# Bagryanets_2.net
KiCad netlist of a schematic drawn in Altium Designer
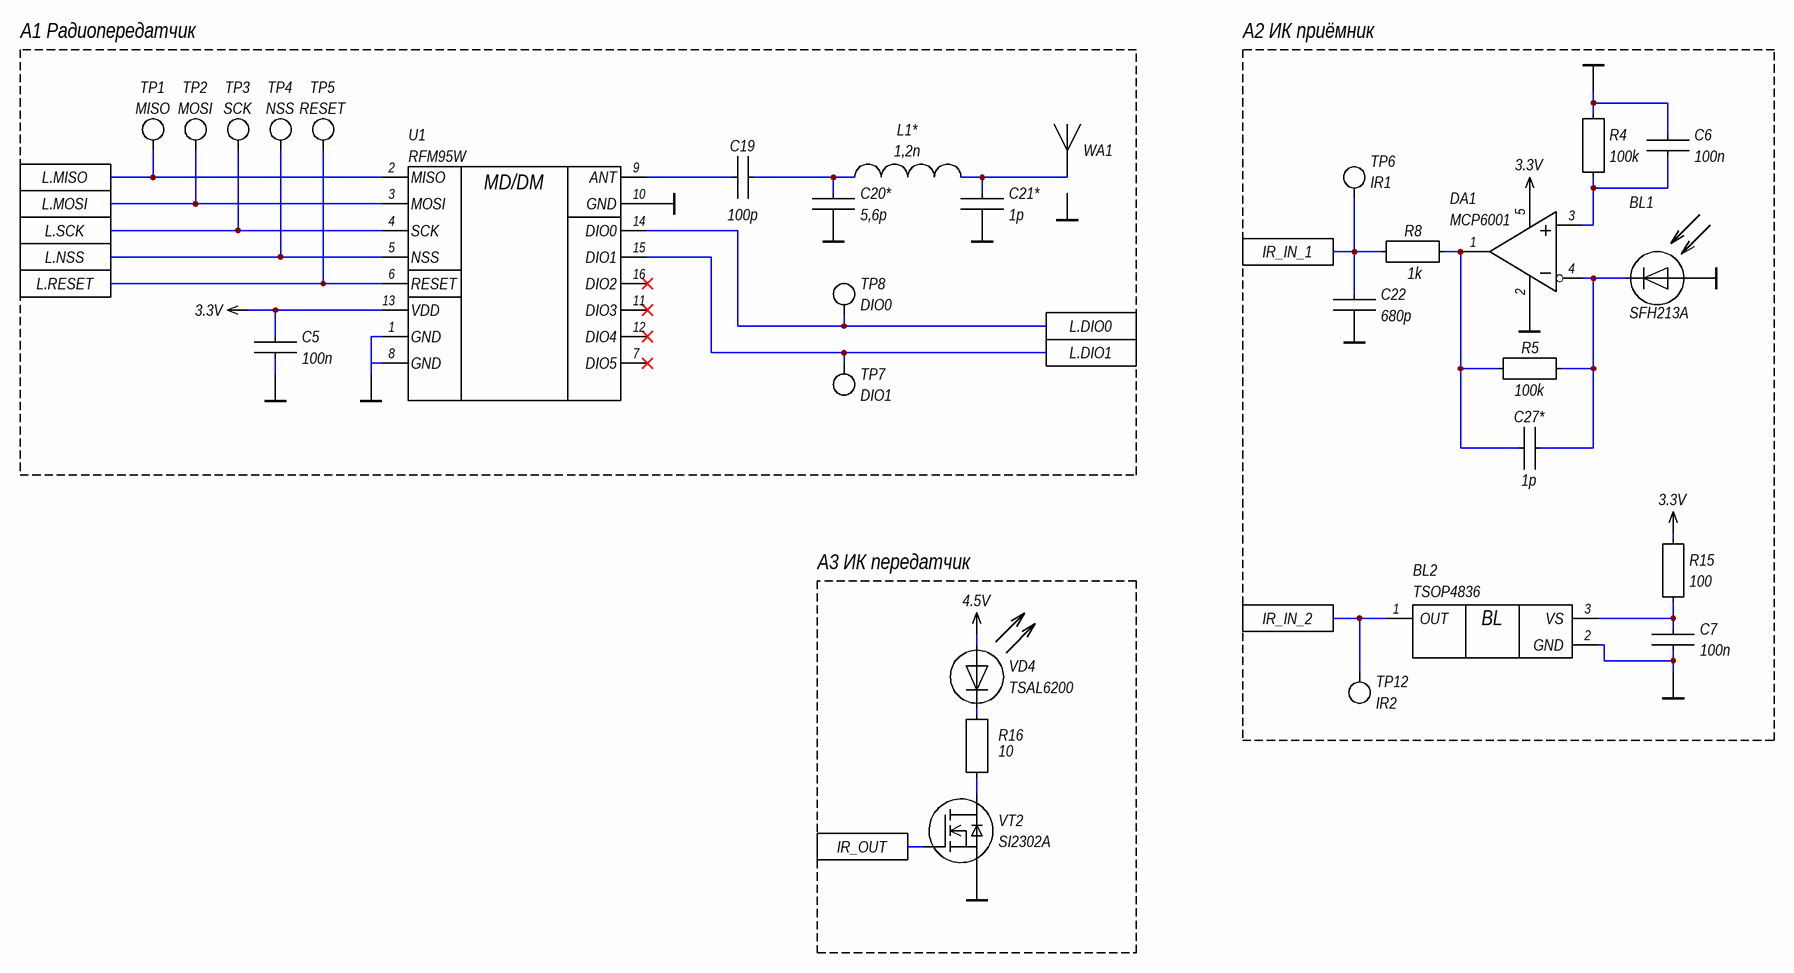
[diagram p0: Bagryanets_2.SchDoc]

(export (version "E")
  (design (tool "Eeschema 10.0.6"))
  (components
    (comp (ref "BL1")
      (value "SFH213A")
      (footprint "LED_5mm")
      (libsource (lib "Bagryanets-Schlib") (part "BL-Photodiod"))
    )
    (comp (ref "BL2")
      (value "TSOP4836")
      (footprint "TO92_TSOP4836_Horizontal")
      (libsource (lib "Bagryanets-Schlib") (part "BL-TSOP4836"))
    )
    (comp (ref "C5")
      (value "100n")
      (footprint "CAP: 0603")
      (libsource (lib "Bagryanets-Schlib") (part "C-Capacitor"))
    )
    (comp (ref "C6")
      (value "100n")
      (footprint "CAP: 0603")
      (libsource (lib "Bagryanets-Schlib") (part "C-Capacitor"))
    )
    (comp (ref "C7")
      (value "100n")
      (footprint "CAP: 0603")
      (libsource (lib "Bagryanets-Schlib") (part "C-Capacitor"))
    )
    (comp (ref "C19")
      (value "100p")
      (footprint "CAP: 0402")
      (libsource (lib "Bagryanets-Schlib") (part "C-Capacitor"))
    )
    (comp (ref "C20*")
      (value "5,6p")
      (footprint "CAP: 0402")
      (libsource (lib "Bagryanets-Schlib") (part "C-Capacitor"))
    )
    (comp (ref "C21*")
      (value "1p")
      (footprint "CAP: 0402")
      (libsource (lib "Bagryanets-Schlib") (part "C-Capacitor"))
    )
    (comp (ref "C22")
      (value "680p")
      (footprint "CAP: 0603")
      (libsource (lib "Bagryanets-Schlib") (part "C-Capacitor"))
    )
    (comp (ref "C27*")
      (value "1p")
      (footprint "CAP: 0603")
      (libsource (lib "Bagryanets-Schlib") (part "C-Capacitor"))
    )
    (comp (ref "DA1")
      (value "MCP6001")
      (footprint "SOT23-5")
      (description "IC OPAMP GP 1 CIRCUIT SOT23-5")
      (fields (field (name "VOLTAGE") "6V"))
      (libsource (lib "Bagryanets-Schlib") (part "DA-MCP6001UT-I/OT"))
    )
    (comp (ref "L1*")
      (value "1,2n")
      (footprint "IND: 0402")
      (libsource (lib "Bagryanets-Schlib") (part "L-Inductor"))
    )
    (comp (ref "R4")
      (value "100k")
      (footprint "RES: 0603")
      (libsource (lib "Bagryanets-Schlib") (part "R-Resistor"))
    )
    (comp (ref "R5")
      (value "100k")
      (footprint "RES: 0603")
      (libsource (lib "Bagryanets-Schlib") (part "R-Resistor"))
    )
    (comp (ref "R8")
      (value "1k")
      (footprint "RES: 0603")
      (libsource (lib "Bagryanets-Schlib") (part "R-Resistor"))
    )
    (comp (ref "R15")
      (value "100")
      (footprint "RES: 0603")
      (libsource (lib "Bagryanets-Schlib") (part "R-Resistor"))
    )
    (comp (ref "R16")
      (value "10")
      (footprint "RES: 0603")
      (libsource (lib "Bagryanets-Schlib") (part "R-Resistor"))
    )
    (comp (ref "TP1")
      (value "MISO")
      (footprint "Testpoint_1mm")
      (libsource (lib "Bagryanets-Schlib") (part "TP-Testpoint"))
    )
    (comp (ref "TP2")
      (value "MOSI")
      (footprint "Testpoint_1mm")
      (libsource (lib "Bagryanets-Schlib") (part "TP-Testpoint"))
    )
    (comp (ref "TP3")
      (value "SCK")
      (footprint "Testpoint_1mm")
      (libsource (lib "Bagryanets-Schlib") (part "TP-Testpoint"))
    )
    (comp (ref "TP4")
      (value "NSS")
      (footprint "Testpoint_1mm")
      (libsource (lib "Bagryanets-Schlib") (part "TP-Testpoint"))
    )
    (comp (ref "TP5")
      (value "RESET")
      (footprint "Testpoint_1mm")
      (libsource (lib "Bagryanets-Schlib") (part "TP-Testpoint"))
    )
    (comp (ref "TP6")
      (value "IR1")
      (footprint "Testpoint_1mm")
      (libsource (lib "Bagryanets-Schlib") (part "TP-Testpoint"))
    )
    (comp (ref "TP7")
      (value "DIO1")
      (footprint "Testpoint_1mm")
      (libsource (lib "Bagryanets-Schlib") (part "TP-Testpoint"))
    )
    (comp (ref "TP8")
      (value "DIO0")
      (footprint "Testpoint_1mm")
      (libsource (lib "Bagryanets-Schlib") (part "TP-Testpoint"))
    )
    (comp (ref "TP12")
      (value "IR2")
      (footprint "Testpoint_1mm")
      (libsource (lib "Bagryanets-Schlib") (part "TP-Testpoint"))
    )
    (comp (ref "U1")
      (value "RFM95W")
      (footprint "Module_RFM95W")
      (description "Rfm95W LoRa Transceiver Module 868Mhz")
      (libsource (lib "Bagryanets-Schlib") (part "MOD-RFM95W"))
    )
    (comp (ref "VD4")
      (value "TSAL6200")
      (footprint "LED_5mm")
      (libsource (lib "Bagryanets-Schlib") (part "HL-LED"))
    )
    (comp (ref "VT2")
      (value "SI2302A")
      (footprint "SOT23")
      (libsource (lib "Bagryanets-Schlib") (part "VT-N-FET-GSD"))
    )
    (comp (ref "WA1")
      (value "Antenna")
      (footprint "WA-Lora868")
      (libsource (lib "Bagryanets-Schlib") (part "WA-Antenna_2pin"))
    )
  )
  (nets
    (net (code "1") (name "/IR_IN_1") (class "Default")
      (node (ref "C22") (pin "2") (pinfunction "2_2") (pintype "passive"))
      (node (ref "R8") (pin "1") (pinfunction "1_1") (pintype "passive"))
      (node (ref "TP6") (pin "1") (pinfunction "1_1") (pintype "passive"))
    )
    (net (code "2") (name "/IR_IN_2") (class "Default")
      (node (ref "BL2") (pin "1") (pinfunction "OUT_1") (pintype "passive"))
      (node (ref "TP12") (pin "1") (pinfunction "1_1") (pintype "passive"))
    )
    (net (code "3") (name "/IR_OUT") (class "Default")
      (node (ref "VT2") (pin "1") (pinfunction "G_1") (pintype "passive"))
    )
    (net (code "4") (name "/L.DIO0") (class "Default")
      (node (ref "TP8") (pin "1") (pinfunction "1_1") (pintype "passive"))
      (node (ref "U1") (pin "14") (pinfunction "DIO0_14") (pintype "passive"))
    )
    (net (code "5") (name "/L.DIO1") (class "Default")
      (node (ref "TP7") (pin "1") (pinfunction "1_1") (pintype "passive"))
      (node (ref "U1") (pin "15") (pinfunction "DIO1_15") (pintype "passive"))
    )
    (net (code "6") (name "/L.MISO") (class "Default")
      (node (ref "TP1") (pin "1") (pinfunction "1_1") (pintype "passive"))
      (node (ref "U1") (pin "2") (pinfunction "MISO_2") (pintype "passive"))
    )
    (net (code "7") (name "/L.MOSI") (class "Default")
      (node (ref "TP2") (pin "1") (pinfunction "1_1") (pintype "passive"))
      (node (ref "U1") (pin "3") (pinfunction "MOSI_3") (pintype "passive"))
    )
    (net (code "8") (name "/L.NSS") (class "Default")
      (node (ref "TP4") (pin "1") (pinfunction "1_1") (pintype "passive"))
      (node (ref "U1") (pin "5") (pinfunction "NSS_5") (pintype "passive"))
    )
    (net (code "9") (name "/L.RESET") (class "Default")
      (node (ref "TP5") (pin "1") (pinfunction "1_1") (pintype "passive"))
      (node (ref "U1") (pin "6") (pinfunction "RESET_6") (pintype "passive"))
    )
    (net (code "10") (name "/L.SCK") (class "Default")
      (node (ref "TP3") (pin "1") (pinfunction "1_1") (pintype "passive"))
      (node (ref "U1") (pin "4") (pinfunction "SCK_4") (pintype "passive"))
    )
    (net (code "11") (name "3.3V") (class "Default")
      (node (ref "C5") (pin "2") (pinfunction "2_2") (pintype "passive"))
      (node (ref "DA1") (pin "5") (pinfunction "VDD_5") (pintype "power_in"))
      (node (ref "R15") (pin "1") (pinfunction "1_1") (pintype "passive"))
      (node (ref "U1") (pin "13") (pinfunction "VDD_13") (pintype "passive"))
    )
    (net (code "12") (name "4.5V") (class "Default")
      (node (ref "VD4") (pin "A") (pinfunction "A_A") (pintype "passive"))
    )
    (net (code "13") (name "GND") (class "Default")
      (node (ref "BL1") (pin "A") (pinfunction "A_A") (pintype "passive"))
      (node (ref "BL2") (pin "2") (pinfunction "GND_2") (pintype "power_in"))
      (node (ref "C20*") (pin "1") (pinfunction "1_1") (pintype "passive"))
      (node (ref "C21*") (pin "1") (pinfunction "1_1") (pintype "passive"))
      (node (ref "C22") (pin "1") (pinfunction "1_1") (pintype "passive"))
      (node (ref "C5") (pin "1") (pinfunction "1_1") (pintype "passive"))
      (node (ref "C6") (pin "2") (pinfunction "2_2") (pintype "passive"))
      (node (ref "C7") (pin "1") (pinfunction "1_1") (pintype "passive"))
      (node (ref "DA1") (pin "2") (pinfunction "VSS_2") (pintype "power_in"))
      (node (ref "R4") (pin "1") (pinfunction "1_1") (pintype "passive"))
      (node (ref "U1") (pin "1") (pinfunction "GND_1") (pintype "passive"))
      (node (ref "U1") (pin "10") (pinfunction "GND_10") (pintype "passive"))
      (node (ref "U1") (pin "8") (pinfunction "GND_8") (pintype "passive"))
      (node (ref "VT2") (pin "2") (pinfunction "S_2") (pintype "passive"))
      (node (ref "WA1") (pin "2") (pinfunction "2_2") (pintype "passive"))
    )
    (net (code "14") (name "Net-(BL2-VS)") (class "Default")
      (node (ref "BL2") (pin "3") (pinfunction "VS_3") (pintype "power_in"))
      (node (ref "C7") (pin "2") (pinfunction "2_2") (pintype "passive"))
      (node (ref "R15") (pin "2") (pinfunction "2_2") (pintype "passive"))
    )
    (net (code "15") (name "Net-(C19-Pad1)") (class "Default")
      (node (ref "C19") (pin "1") (pinfunction "1_1") (pintype "passive"))
      (node (ref "C20*") (pin "2") (pinfunction "2_2") (pintype "passive"))
      (node (ref "L1*") (pin "1") (pinfunction "1_1") (pintype "passive"))
    )
    (net (code "16") (name "Net-(C21*-Pad2)") (class "Default")
      (node (ref "C21*") (pin "2") (pinfunction "2_2") (pintype "passive"))
      (node (ref "L1*") (pin "2") (pinfunction "2_2") (pintype "passive"))
      (node (ref "WA1") (pin "1") (pinfunction "1_1") (pintype "passive"))
    )
    (net (code "17") (name "Net-(DA1-VIN+)") (class "Default")
      (node (ref "C6") (pin "1") (pinfunction "1_1") (pintype "passive"))
      (node (ref "DA1") (pin "3") (pinfunction "VIN+_3") (pintype "passive"))
      (node (ref "R4") (pin "2") (pinfunction "2_2") (pintype "passive"))
    )
    (net (code "18") (name "Net-(DA1-VIN-)") (class "Default")
      (node (ref "BL1") (pin "C") (pinfunction "C_C") (pintype "passive"))
      (node (ref "C27*") (pin "2") (pinfunction "2_2") (pintype "passive"))
      (node (ref "DA1") (pin "4") (pinfunction "VIN-_4") (pintype "passive"))
      (node (ref "R5") (pin "2") (pinfunction "2_2") (pintype "passive"))
    )
    (net (code "19") (name "Net-(DA1-VOUT)") (class "Default")
      (node (ref "C27*") (pin "1") (pinfunction "1_1") (pintype "passive"))
      (node (ref "DA1") (pin "1") (pinfunction "VOUT_1") (pintype "passive"))
      (node (ref "R5") (pin "1") (pinfunction "1_1") (pintype "passive"))
      (node (ref "R8") (pin "2") (pinfunction "2_2") (pintype "passive"))
    )
    (net (code "20") (name "Net-(R16-Pad1)") (class "Default")
      (node (ref "R16") (pin "1") (pinfunction "1_1") (pintype "passive"))
      (node (ref "VD4") (pin "C") (pinfunction "C_C") (pintype "passive"))
    )
    (net (code "21") (name "Net-(U1-ANT)") (class "Default")
      (node (ref "C19") (pin "2") (pinfunction "2_2") (pintype "passive"))
      (node (ref "U1") (pin "9") (pinfunction "ANT_9") (pintype "passive"))
    )
    (net (code "22") (name "Net-(VT2-D)") (class "Default")
      (node (ref "R16") (pin "2") (pinfunction "2_2") (pintype "passive"))
      (node (ref "VT2") (pin "3") (pinfunction "D_3") (pintype "passive"))
    )
    (net (code "23") (name "unconnected-(U1-DIO2-Pad16)") (class "Default")
      (node (ref "U1") (pin "16") (pinfunction "DIO2_16") (pintype "passive+no_connect"))
    )
    (net (code "24") (name "unconnected-(U1-DIO3-Pad11)") (class "Default")
      (node (ref "U1") (pin "11") (pinfunction "DIO3_11") (pintype "passive+no_connect"))
    )
    (net (code "25") (name "unconnected-(U1-DIO4-Pad12)") (class "Default")
      (node (ref "U1") (pin "12") (pinfunction "DIO4_12") (pintype "passive+no_connect"))
    )
    (net (code "26") (name "unconnected-(U1-DIO5-Pad7)") (class "Default")
      (node (ref "U1") (pin "7") (pinfunction "DIO5_7") (pintype "passive+no_connect"))
    )
  )
)
